# filter-2.net
KiCad netlist of a schematic drawn in Altium Designer
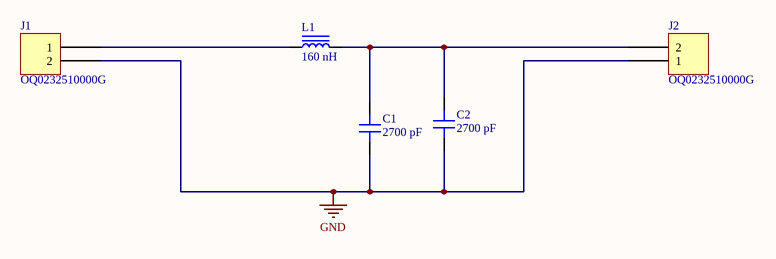
[diagram p0: filter-2.SchDoc]

(export (version "E")
  (design (tool "Eeschema 10.0.6"))
  (components
    (comp (ref "C1")
      (value "2700 pF")
      (footprint "CAP 0603_1608")
      (description "CAP CER 2700PF 25V NP0 0603")
      (fields (field (name "PART NUMBER") "C0603C272F3GAC7867") (field (name "MANUFACTURER") "KEMET"))
      (libsource (lib "Celestial Altium Library - altium_library") (part "Capacitor"))
    )
    (comp (ref "C2")
      (value "2700 pF")
      (footprint "CAP 0603_1608")
      (description "CAP CER 2700PF 25V NP0 0603")
      (fields (field (name "PART NUMBER") "C0603C272F3GAC7867") (field (name "MANUFACTURER") "KEMET"))
      (libsource (lib "Celestial Altium Library - altium_library") (part "Capacitor"))
    )
    (comp (ref "J1")
      (value "OQ0232510000G")
      (footprint "FCI 06-381-2PIN")
      (description "TERM BLOCK HDR 2POS 90DEG 3.81MM")
      (fields (field (name "MANUFACTURER") "Amphenol Anytek"))
      (libsource (lib "") (part "2 Pin_1"))
    )
    (comp (ref "J2")
      (value "OQ0232510000G")
      (footprint "FCI 06-381-2PIN")
      (description "TERM BLOCK HDR 2POS 90DEG 3.81MM")
      (fields (field (name "MANUFACTURER") "Amphenol Anytek"))
      (libsource (lib "Celestial Altium Library - altium_library") (part "2 Pin"))
    )
    (comp (ref "L1")
      (value "160 nH")
      (footprint "IND 0402_1005 RF WW")
      (description "FIXED IND 160NH 480MA 330MOHM SM")
      (fields
        (field (name "PART NUMBER") "LQW15CNR16J00D")
        (field (name "MANUFACTURER") "Murata Electronics")
      )
      (libsource (lib "Celestial Altium Library - altium_library") (part "Inductor"))
    )
  )
  (nets
    (net (code "1") (name "GND") (class "Default")
      (node (ref "C1") (pin "1") (pinfunction "1_1") (pintype "passive"))
      (node (ref "C2") (pin "1") (pinfunction "1_1") (pintype "passive"))
      (node (ref "J1") (pin "2") (pinfunction "2_2") (pintype "passive"))
      (node (ref "J2") (pin "1") (pinfunction "1_1") (pintype "passive"))
    )
    (net (code "2") (name "Net-(C1-Pad2)") (class "Default")
      (node (ref "C1") (pin "2") (pinfunction "2_2") (pintype "passive"))
      (node (ref "C2") (pin "2") (pinfunction "2_2") (pintype "passive"))
      (node (ref "J2") (pin "2") (pinfunction "2_2") (pintype "passive"))
      (node (ref "L1") (pin "2") (pinfunction "2_2") (pintype "passive"))
    )
    (net (code "3") (name "Net-(J1-Pad1)") (class "Default")
      (node (ref "J1") (pin "1") (pinfunction "1_1") (pintype "passive"))
      (node (ref "L1") (pin "1") (pinfunction "1_1") (pintype "passive"))
    )
  )
)
